# Proto-Pi.net
KiCad netlist of a schematic drawn in EAGLE
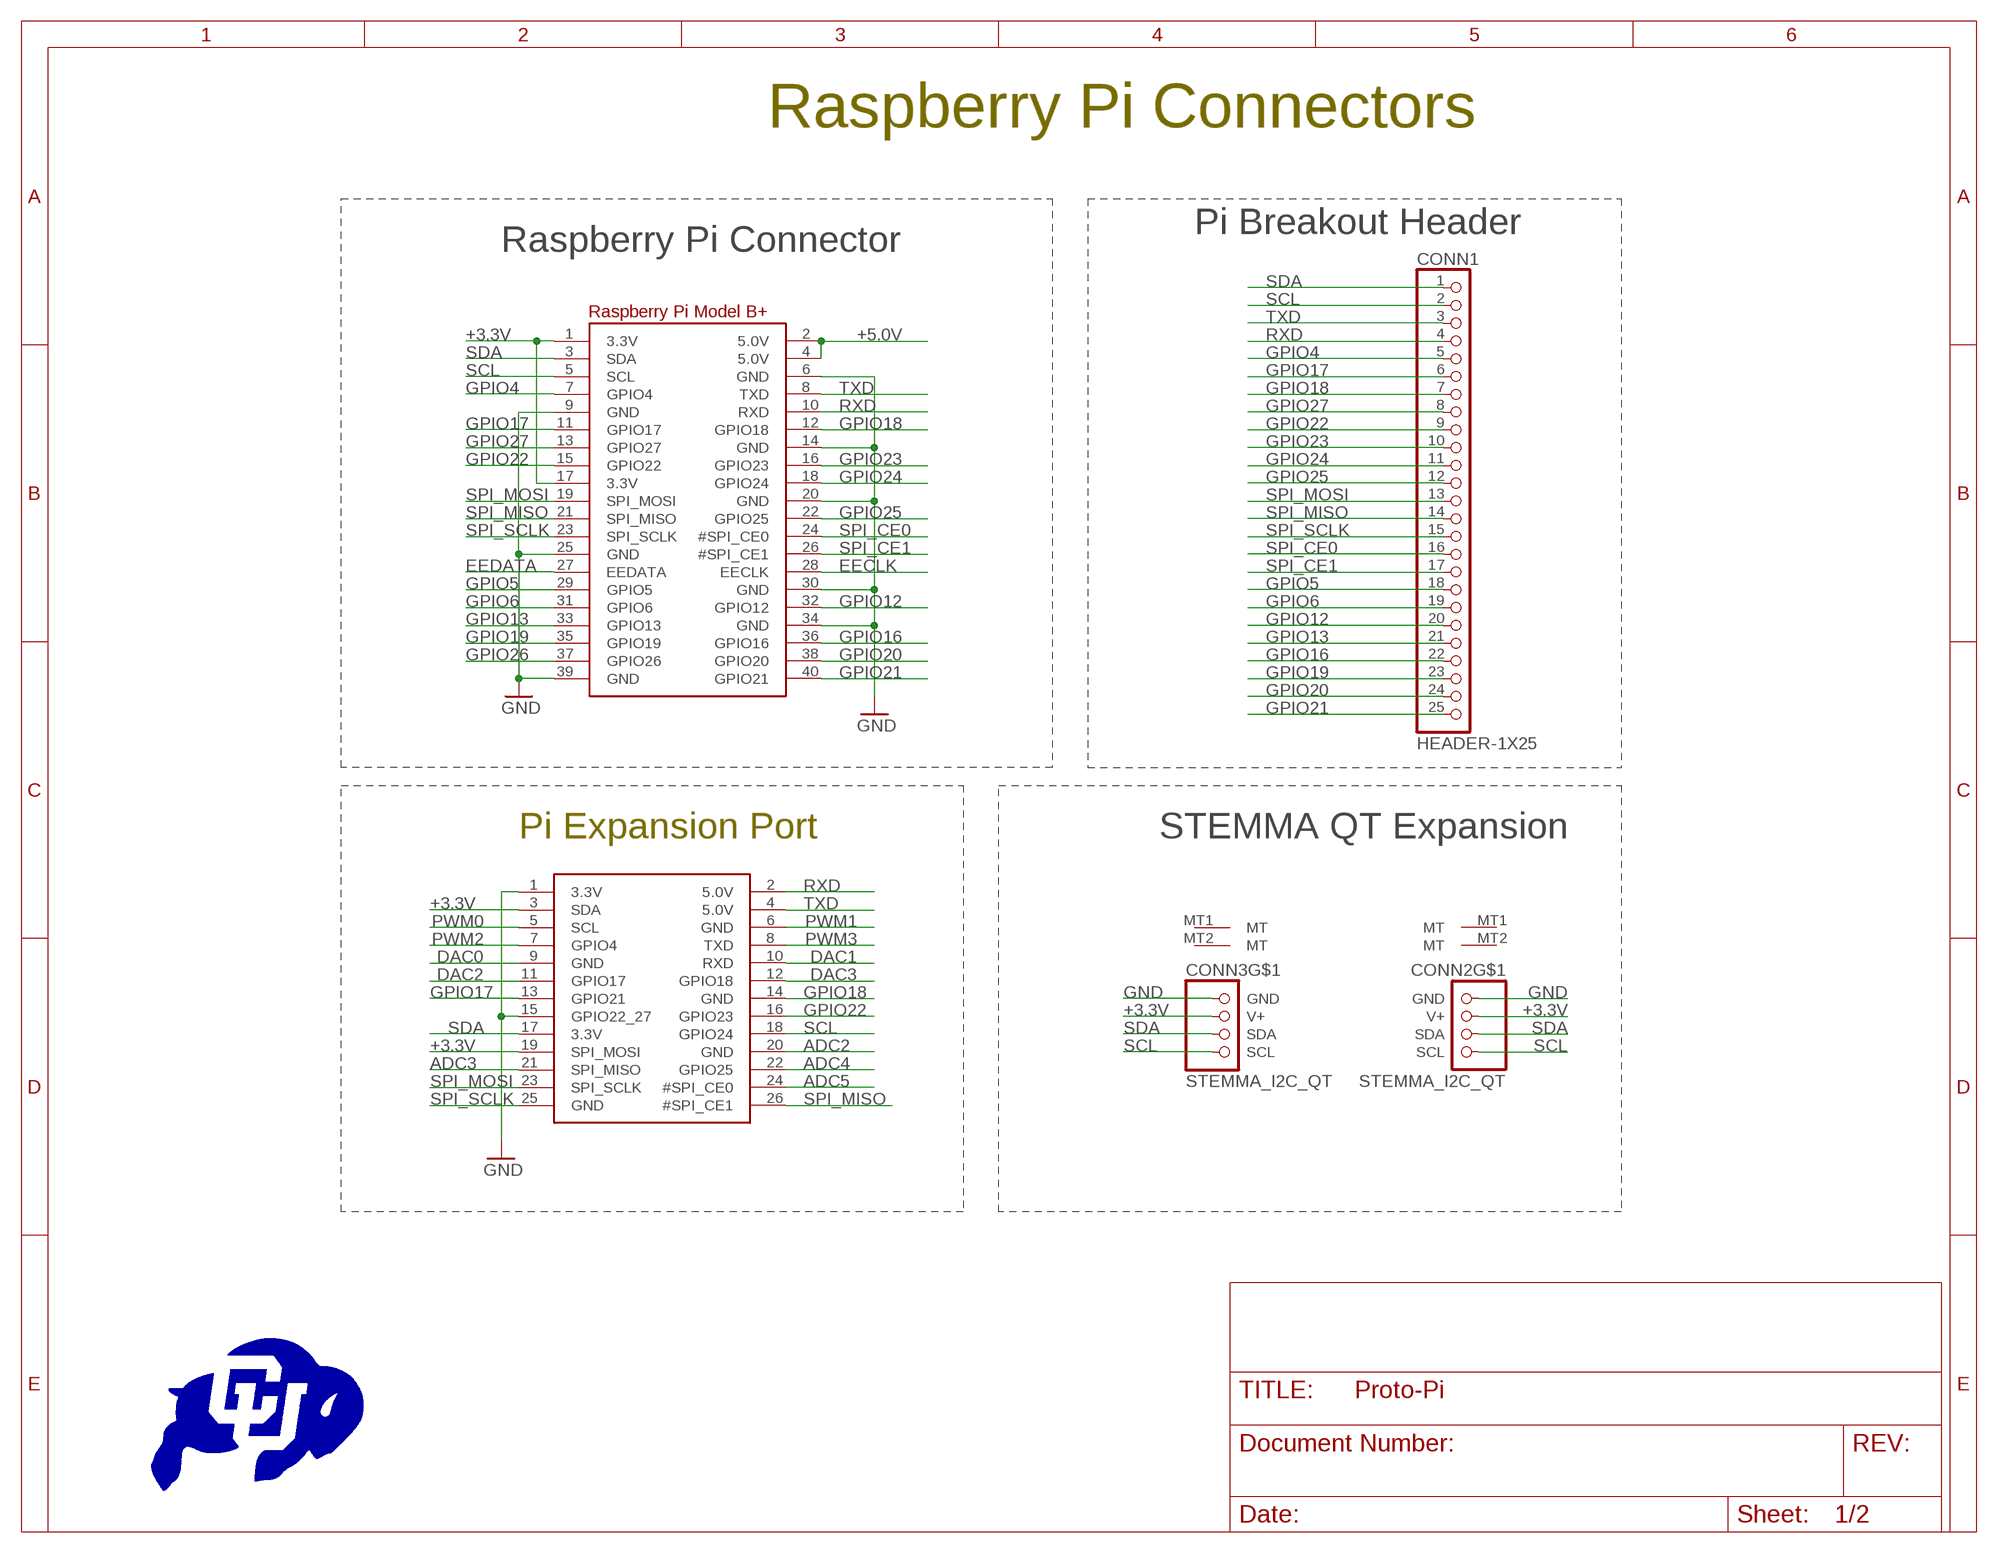
[diagram p0: schematic, sheet 1]
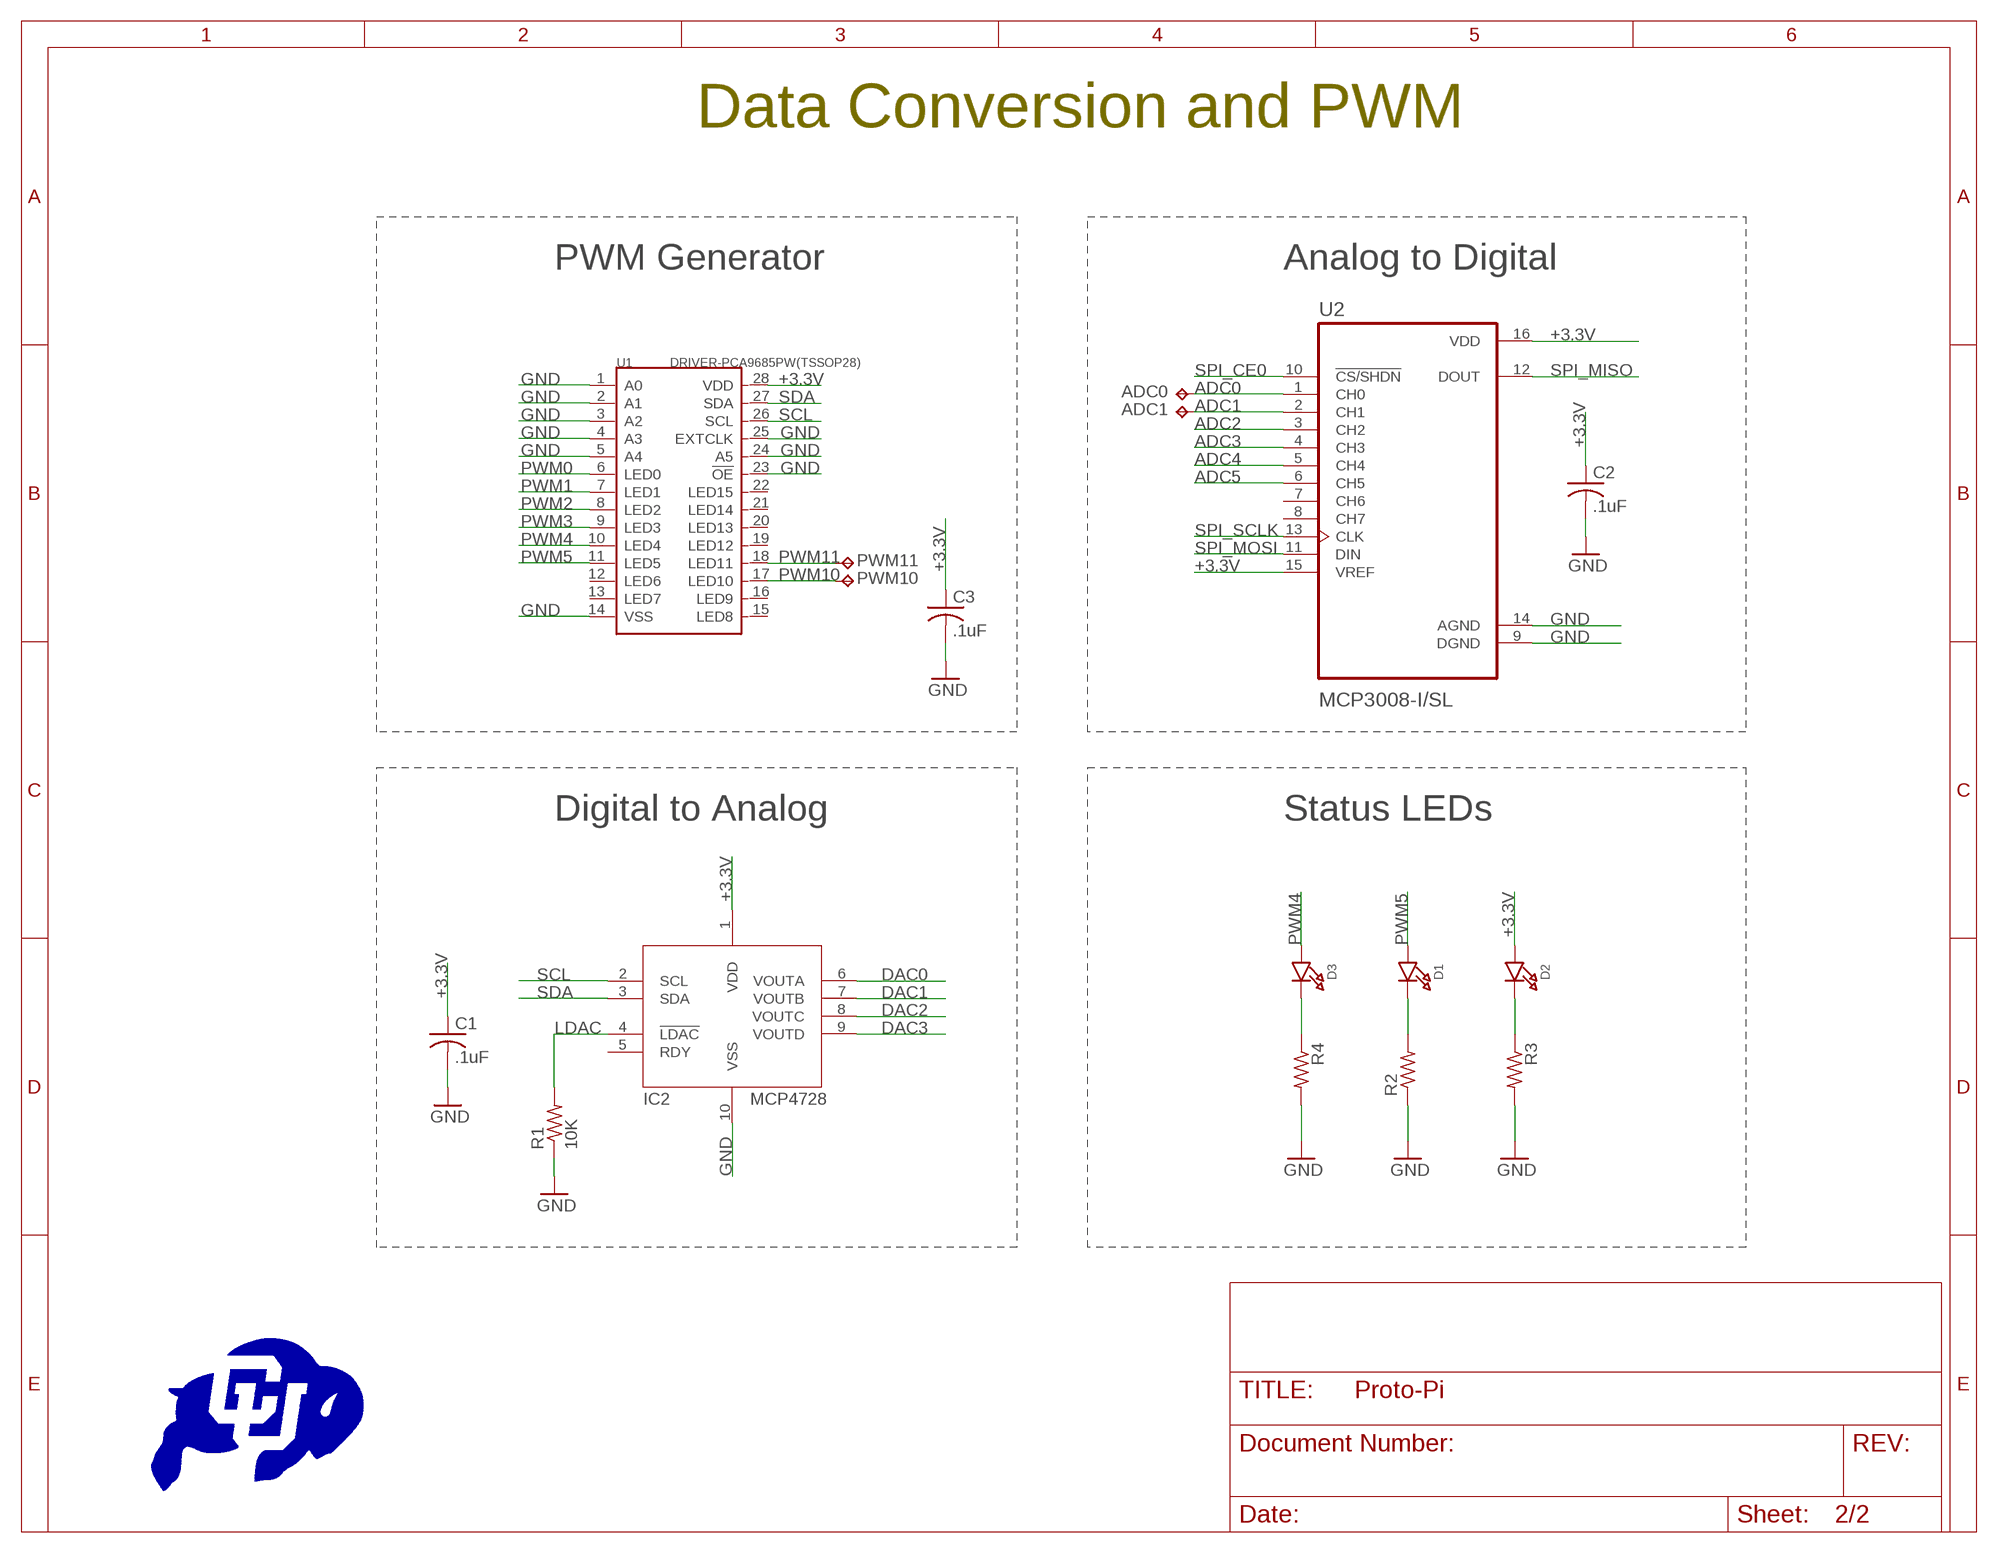
[diagram p1: schematic, sheet 2]

(export (version "E")
  (design (tool "Eeschema 10.0.6"))
  (components
    (comp (ref "CONN1")
      (value "HEADER-1X25")
      (footprint "eagle-import:1X25_ROUND_70MIL")
      (libsource (lib "eagle-import") (part "HEADER-1X25"))
    )
    (comp (ref "CONN2")
      (value "STEMMA_I2C_QT")
      (footprint "eagle-import:JST_SH4")
      (libsource (lib "eagle-import") (part "STEMMA_I2C_QT"))
    )
    (comp (ref "CONN3")
      (value "STEMMA_I2C_QT")
      (footprint "eagle-import:JST_SH4")
      (libsource (lib "eagle-import") (part "STEMMA_I2C_QT"))
    )
    (comp (ref "JP1")
      (value "RASBERRYPI_IDC")
      (footprint "eagle-import:RASBERRYPI_IDC")
      (libsource (lib "eagle-import") (part "RASBERRYPI_IDC"))
    )
    (comp (ref "P1")
      (value "ART-CU-LOGO")
      (footprint "eagle-import:CU_LOGO")
      (libsource (lib "eagle-import") (part "ART-CU-LOGO"))
    )
    (comp (ref "RPI1")
      (value "RASPBERRYPI_BPLUS_BONNETNODIM")
      (footprint "eagle-import:PI_BONNET_NODIM")
      (libsource (lib "eagle-import") (part "RASPBERRYPI_BPLUS_BONNETNODIM"))
    )
    (comp (ref "ADC0")
      (value "TPTP20R")
      (footprint "eagle-import:TP20R")
      (libsource (lib "eagle-import") (part "TPTP20R"))
    )
    (comp (ref "ADC1")
      (value "TPTP20R")
      (footprint "eagle-import:TP20R")
      (libsource (lib "eagle-import") (part "TPTP20R"))
    )
    (comp (ref "C1")
      (value ".1uF")
      (footprint "eagle-import:C0603")
      (fields (field (name "MANUFACTURER") "?"))
      (libsource (lib "eagle-import") (part "C-USC0603"))
    )
    (comp (ref "C2")
      (value ".1uF")
      (footprint "eagle-import:C0603")
      (fields (field (name "MANUFACTURER") "?"))
      (libsource (lib "eagle-import") (part "C-USC0603"))
    )
    (comp (ref "C3")
      (value ".1uF")
      (footprint "eagle-import:C0603")
      (fields (field (name "MANUFACTURER") "?"))
      (libsource (lib "eagle-import") (part "C-USC0603"))
    )
    (comp (ref "D1")
      (value "LED0603_NOOUTLINE")
      (footprint "eagle-import:CHIPLED_0603_NOOUTLINE")
      (libsource (lib "eagle-import") (part "LED0603_NOOUTLINE"))
    )
    (comp (ref "D2")
      (value "LED0603_NOOUTLINE")
      (footprint "eagle-import:CHIPLED_0603_NOOUTLINE")
      (libsource (lib "eagle-import") (part "LED0603_NOOUTLINE"))
    )
    (comp (ref "D3")
      (value "LED0603_NOOUTLINE")
      (footprint "eagle-import:CHIPLED_0603_NOOUTLINE")
      (libsource (lib "eagle-import") (part "LED0603_NOOUTLINE"))
    )
    (comp (ref "IC2")
      (value "MCP4728")
      (footprint "eagle-import:MSOP10")
      (libsource (lib "eagle-import") (part "MCP4728"))
    )
    (comp (ref "P2")
      (value "ART-CU-LOGO")
      (footprint "eagle-import:CU_LOGO")
      (libsource (lib "eagle-import") (part "ART-CU-LOGO"))
    )
    (comp (ref "PWM10")
      (value "TPTP20R")
      (footprint "eagle-import:TP20R")
      (libsource (lib "eagle-import") (part "TPTP20R"))
    )
    (comp (ref "PWM11")
      (value "TPTP20R")
      (footprint "eagle-import:TP20R")
      (libsource (lib "eagle-import") (part "TPTP20R"))
    )
    (comp (ref "R1")
      (value "10K")
      (footprint "eagle-import:R0603")
      (fields (field (name "MANUFACTURER") "?"))
      (libsource (lib "eagle-import") (part "RLC_33165012_R-US_R0603"))
    )
    (comp (ref "R2")
      (value "R-US_R0402")
      (footprint "eagle-import:R0402")
      (fields (field (name "MANUFACTURER") "?"))
      (libsource (lib "eagle-import") (part "R-US_R0402"))
    )
    (comp (ref "R3")
      (value "R-US_R0402")
      (footprint "eagle-import:R0402")
      (fields (field (name "MANUFACTURER") "?"))
      (libsource (lib "eagle-import") (part "R-US_R0402"))
    )
    (comp (ref "R4")
      (value "R-US_R0402")
      (footprint "eagle-import:R0402")
      (fields (field (name "MANUFACTURER") "?"))
      (libsource (lib "eagle-import") (part "R-US_R0402"))
    )
    (comp (ref "U1")
      (value "DRIVER-PCA9685PW(TSSOP28)")
      (footprint "eagle-import:TSSOP28-0.65-9.7X4.4MM")
      (fields (field (name "MF") "NXP USA") (field (name "MP") "PCA9685PW"))
      (libsource (lib "eagle-import") (part "DRIVER-PCA9685PW(TSSOP28)"))
    )
    (comp (ref "U2")
      (value "MCP3008-I/SL")
      (footprint "eagle-import:SOIC127P600X175-16N")
      (fields (field (name "MF") "Microchip Technology"))
      (libsource (lib "eagle-import") (part "MCP3008-I/SL"))
    )
  )
  (nets
    (net (code "1") (name "+3.3V") (class "Default")
      (node (ref "C1") (pin "1") (pinfunction "1_1") (pintype "passive"))
      (node (ref "C2") (pin "1") (pinfunction "1_1") (pintype "passive"))
      (node (ref "C3") (pin "1") (pinfunction "1_1") (pintype "passive"))
      (node (ref "CONN2") (pin "2") (pinfunction "V+_2") (pintype "passive"))
      (node (ref "CONN3") (pin "2") (pinfunction "V+_2") (pintype "passive"))
      (node (ref "D2") (pin "A") (pinfunction "A_A") (pintype "passive"))
      (node (ref "IC2") (pin "1") (pinfunction "VDD_1") (pintype "power_in"))
      (node (ref "JP1") (pin "19") (pinfunction "SPI_MOSI_19") (pintype "bidirectional"))
      (node (ref "JP1") (pin "3") (pinfunction "SDA_3") (pintype "bidirectional"))
      (node (ref "RPI1") (pin "1") (pinfunction "3.3V_1") (pintype "power_in"))
      (node (ref "RPI1") (pin "17") (pinfunction "3.3V_17") (pintype "power_in"))
      (node (ref "U1") (pin "28") (pinfunction "VDD_28") (pintype "bidirectional"))
      (node (ref "U2") (pin "15") (pinfunction "VREF_15") (pintype "input"))
      (node (ref "U2") (pin "16") (pinfunction "VDD_16") (pintype "power_in"))
    )
    (net (code "2") (name "+5.0V") (class "Default")
      (node (ref "RPI1") (pin "2") (pinfunction "5.0V_2") (pintype "power_in"))
      (node (ref "RPI1") (pin "4") (pinfunction "5.0V_4") (pintype "power_in"))
    )
    (net (code "3") (name "ADC0") (class "Default")
      (node (ref "ADC0") (pin "TP") (pinfunction "TP_TP") (pintype "input"))
      (node (ref "U2") (pin "1") (pinfunction "CH0_1") (pintype "input"))
    )
    (net (code "4") (name "ADC1") (class "Default")
      (node (ref "ADC1") (pin "TP") (pinfunction "TP_TP") (pintype "input"))
      (node (ref "U2") (pin "2") (pinfunction "CH1_2") (pintype "input"))
    )
    (net (code "5") (name "ADC2") (class "Default")
      (node (ref "JP1") (pin "20") (pinfunction "GND_20") (pintype "power_in"))
      (node (ref "U2") (pin "3") (pinfunction "CH2_3") (pintype "input"))
    )
    (net (code "6") (name "ADC3") (class "Default")
      (node (ref "JP1") (pin "21") (pinfunction "SPI_MISO_21") (pintype "input"))
      (node (ref "U2") (pin "4") (pinfunction "CH3_4") (pintype "input"))
    )
    (net (code "7") (name "ADC4") (class "Default")
      (node (ref "JP1") (pin "22") (pinfunction "GPIO25_22") (pintype "bidirectional"))
      (node (ref "U2") (pin "5") (pinfunction "CH4_5") (pintype "input"))
    )
    (net (code "8") (name "ADC5") (class "Default")
      (node (ref "JP1") (pin "24") (pinfunction "#SPI_CE0_24") (pintype "bidirectional"))
      (node (ref "U2") (pin "6") (pinfunction "CH5_6") (pintype "input"))
    )
    (net (code "9") (name "DAC0") (class "Default")
      (node (ref "IC2") (pin "6") (pinfunction "VOUTA_6") (pintype "output"))
      (node (ref "JP1") (pin "9") (pinfunction "GND_9") (pintype "power_in"))
    )
    (net (code "10") (name "DAC1") (class "Default")
      (node (ref "IC2") (pin "7") (pinfunction "VOUTB_7") (pintype "output"))
      (node (ref "JP1") (pin "10") (pinfunction "RXD_10") (pintype "input"))
    )
    (net (code "11") (name "DAC2") (class "Default")
      (node (ref "IC2") (pin "8") (pinfunction "VOUTC_8") (pintype "output"))
      (node (ref "JP1") (pin "11") (pinfunction "GPIO17_11") (pintype "bidirectional"))
    )
    (net (code "12") (name "DAC3") (class "Default")
      (node (ref "IC2") (pin "9") (pinfunction "VOUTD_9") (pintype "output"))
      (node (ref "JP1") (pin "12") (pinfunction "GPIO18_12") (pintype "bidirectional"))
    )
    (net (code "13") (name "EECLK") (class "Default")
      (node (ref "RPI1") (pin "28") (pinfunction "EECLK_28") (pintype "bidirectional"))
    )
    (net (code "14") (name "EEDATA") (class "Default")
      (node (ref "RPI1") (pin "27") (pinfunction "EEDATA_27") (pintype "bidirectional"))
    )
    (net (code "15") (name "GND") (class "Default")
      (node (ref "C1") (pin "2") (pinfunction "2_2") (pintype "passive"))
      (node (ref "C2") (pin "2") (pinfunction "2_2") (pintype "passive"))
      (node (ref "C3") (pin "2") (pinfunction "2_2") (pintype "passive"))
      (node (ref "CONN2") (pin "1") (pinfunction "GND_1") (pintype "passive"))
      (node (ref "CONN3") (pin "1") (pinfunction "GND_1") (pintype "passive"))
      (node (ref "IC2") (pin "10") (pinfunction "VSS_10") (pintype "power_in"))
      (node (ref "JP1") (pin "1") (pinfunction "3.3V_1") (pintype "power_in"))
      (node (ref "JP1") (pin "15") (pinfunction "GPIO22_27_15") (pintype "bidirectional"))
      (node (ref "R1") (pin "1") (pinfunction "1_1") (pintype "passive"))
      (node (ref "R2") (pin "1") (pinfunction "1_1") (pintype "passive"))
      (node (ref "R3") (pin "2") (pinfunction "2_2") (pintype "passive"))
      (node (ref "R4") (pin "2") (pinfunction "2_2") (pintype "passive"))
      (node (ref "RPI1") (pin "14") (pinfunction "GND_14") (pintype "power_in"))
      (node (ref "RPI1") (pin "20") (pinfunction "GND_20") (pintype "power_in"))
      (node (ref "RPI1") (pin "25") (pinfunction "GND_25") (pintype "power_in"))
      (node (ref "RPI1") (pin "30") (pinfunction "GND_30") (pintype "power_in"))
      (node (ref "RPI1") (pin "34") (pinfunction "GND_34") (pintype "power_in"))
      (node (ref "RPI1") (pin "39") (pinfunction "GND_39") (pintype "power_in"))
      (node (ref "RPI1") (pin "6") (pinfunction "GND_6") (pintype "power_in"))
      (node (ref "RPI1") (pin "9") (pinfunction "GND_9") (pintype "power_in"))
      (node (ref "U1") (pin "1") (pinfunction "A0_1") (pintype "bidirectional"))
      (node (ref "U1") (pin "14") (pinfunction "VSS_14") (pintype "bidirectional"))
      (node (ref "U1") (pin "2") (pinfunction "A1_2") (pintype "bidirectional"))
      (node (ref "U1") (pin "23") (pinfunction "~{OE}_23") (pintype "bidirectional"))
      (node (ref "U1") (pin "24") (pinfunction "A5_24") (pintype "bidirectional"))
      (node (ref "U1") (pin "25") (pinfunction "EXTCLK_25") (pintype "bidirectional"))
      (node (ref "U1") (pin "3") (pinfunction "A2_3") (pintype "bidirectional"))
      (node (ref "U1") (pin "4") (pinfunction "A3_4") (pintype "bidirectional"))
      (node (ref "U1") (pin "5") (pinfunction "A4_5") (pintype "bidirectional"))
      (node (ref "U2") (pin "14") (pinfunction "AGND_14") (pintype "power_in"))
      (node (ref "U2") (pin "9") (pinfunction "DGND_9") (pintype "power_in"))
    )
    (net (code "16") (name "GPIO4") (class "Default")
      (node (ref "CONN1") (pin "5") (pinfunction "5_5") (pintype "passive"))
      (node (ref "RPI1") (pin "7") (pinfunction "GPIO4_7") (pintype "bidirectional"))
    )
    (net (code "17") (name "GPIO5") (class "Default")
      (node (ref "CONN1") (pin "18") (pinfunction "18_18") (pintype "passive"))
      (node (ref "RPI1") (pin "29") (pinfunction "GPIO5_29") (pintype "bidirectional"))
    )
    (net (code "18") (name "GPIO6") (class "Default")
      (node (ref "CONN1") (pin "19") (pinfunction "19_19") (pintype "passive"))
      (node (ref "RPI1") (pin "31") (pinfunction "GPIO6_31") (pintype "bidirectional"))
    )
    (net (code "19") (name "GPIO12") (class "Default")
      (node (ref "CONN1") (pin "20") (pinfunction "20_20") (pintype "passive"))
      (node (ref "RPI1") (pin "32") (pinfunction "GPIO12_32") (pintype "bidirectional"))
    )
    (net (code "20") (name "GPIO13") (class "Default")
      (node (ref "CONN1") (pin "21") (pinfunction "21_21") (pintype "passive"))
      (node (ref "RPI1") (pin "33") (pinfunction "GPIO13_33") (pintype "bidirectional"))
    )
    (net (code "21") (name "GPIO16") (class "Default")
      (node (ref "CONN1") (pin "22") (pinfunction "22_22") (pintype "passive"))
      (node (ref "RPI1") (pin "36") (pinfunction "GPIO16_36") (pintype "bidirectional"))
    )
    (net (code "22") (name "GPIO17") (class "Default")
      (node (ref "CONN1") (pin "6") (pinfunction "6_6") (pintype "passive"))
      (node (ref "JP1") (pin "13") (pinfunction "GPIO21_13") (pintype "bidirectional"))
      (node (ref "RPI1") (pin "11") (pinfunction "GPIO17_11") (pintype "bidirectional"))
    )
    (net (code "23") (name "GPIO18") (class "Default")
      (node (ref "CONN1") (pin "7") (pinfunction "7_7") (pintype "passive"))
      (node (ref "JP1") (pin "14") (pinfunction "GND_14") (pintype "power_in"))
      (node (ref "RPI1") (pin "12") (pinfunction "GPIO18_12") (pintype "bidirectional"))
    )
    (net (code "24") (name "GPIO19") (class "Default")
      (node (ref "CONN1") (pin "23") (pinfunction "23_23") (pintype "passive"))
      (node (ref "RPI1") (pin "35") (pinfunction "GPIO19_35") (pintype "bidirectional"))
    )
    (net (code "25") (name "GPIO20") (class "Default")
      (node (ref "CONN1") (pin "24") (pinfunction "24_24") (pintype "passive"))
      (node (ref "RPI1") (pin "38") (pinfunction "GPIO20_38") (pintype "bidirectional"))
    )
    (net (code "26") (name "GPIO21") (class "Default")
      (node (ref "CONN1") (pin "25") (pinfunction "25_25") (pintype "passive"))
      (node (ref "RPI1") (pin "40") (pinfunction "GPIO21_40") (pintype "bidirectional"))
    )
    (net (code "27") (name "GPIO22") (class "Default")
      (node (ref "CONN1") (pin "9") (pinfunction "9_9") (pintype "passive"))
      (node (ref "JP1") (pin "16") (pinfunction "GPIO23_16") (pintype "bidirectional"))
      (node (ref "RPI1") (pin "15") (pinfunction "GPIO22_15") (pintype "bidirectional"))
    )
    (net (code "28") (name "GPIO23") (class "Default")
      (node (ref "CONN1") (pin "10") (pinfunction "10_10") (pintype "passive"))
      (node (ref "RPI1") (pin "16") (pinfunction "GPIO23_16") (pintype "bidirectional"))
    )
    (net (code "29") (name "GPIO24") (class "Default")
      (node (ref "CONN1") (pin "11") (pinfunction "11_11") (pintype "passive"))
      (node (ref "RPI1") (pin "18") (pinfunction "GPIO24_18") (pintype "bidirectional"))
    )
    (net (code "30") (name "GPIO25") (class "Default")
      (node (ref "CONN1") (pin "12") (pinfunction "12_12") (pintype "passive"))
      (node (ref "RPI1") (pin "22") (pinfunction "GPIO25_22") (pintype "bidirectional"))
    )
    (net (code "31") (name "GPIO26") (class "Default")
      (node (ref "RPI1") (pin "37") (pinfunction "GPIO26_37") (pintype "bidirectional"))
    )
    (net (code "32") (name "GPIO27") (class "Default")
      (node (ref "CONN1") (pin "8") (pinfunction "8_8") (pintype "passive"))
      (node (ref "RPI1") (pin "13") (pinfunction "GPIO27_13") (pintype "bidirectional"))
    )
    (net (code "33") (name "LDAC") (class "Default")
      (node (ref "IC2") (pin "4") (pinfunction "~{LDAC}_4") (pintype "input"))
      (node (ref "R1") (pin "2") (pinfunction "2_2") (pintype "passive"))
    )
    (net (code "34") (name "Net-(D1-PadC)") (class "Default")
      (node (ref "D1") (pin "C") (pinfunction "C_C") (pintype "passive"))
      (node (ref "R2") (pin "2") (pinfunction "2_2") (pintype "passive"))
    )
    (net (code "35") (name "Net-(D2-PadC)") (class "Default")
      (node (ref "D2") (pin "C") (pinfunction "C_C") (pintype "passive"))
      (node (ref "R3") (pin "1") (pinfunction "1_1") (pintype "passive"))
    )
    (net (code "36") (name "Net-(D3-PadC)") (class "Default")
      (node (ref "D3") (pin "C") (pinfunction "C_C") (pintype "passive"))
      (node (ref "R4") (pin "1") (pinfunction "1_1") (pintype "passive"))
    )
    (net (code "37") (name "PWM0") (class "Default")
      (node (ref "JP1") (pin "5") (pinfunction "SCL_5") (pintype "bidirectional"))
      (node (ref "U1") (pin "6") (pinfunction "LED0_6") (pintype "bidirectional"))
    )
    (net (code "38") (name "PWM1") (class "Default")
      (node (ref "JP1") (pin "6") (pinfunction "GND_6") (pintype "power_in"))
      (node (ref "U1") (pin "7") (pinfunction "LED1_7") (pintype "bidirectional"))
    )
    (net (code "39") (name "PWM2") (class "Default")
      (node (ref "JP1") (pin "7") (pinfunction "GPIO4_7") (pintype "bidirectional"))
      (node (ref "U1") (pin "8") (pinfunction "LED2_8") (pintype "bidirectional"))
    )
    (net (code "40") (name "PWM3") (class "Default")
      (node (ref "JP1") (pin "8") (pinfunction "TXD_8") (pintype "output"))
      (node (ref "U1") (pin "9") (pinfunction "LED3_9") (pintype "bidirectional"))
    )
    (net (code "41") (name "PWM4") (class "Default")
      (node (ref "D3") (pin "A") (pinfunction "A_A") (pintype "passive"))
      (node (ref "U1") (pin "10") (pinfunction "LED4_10") (pintype "bidirectional"))
    )
    (net (code "42") (name "PWM5") (class "Default")
      (node (ref "D1") (pin "A") (pinfunction "A_A") (pintype "passive"))
      (node (ref "U1") (pin "11") (pinfunction "LED5_11") (pintype "bidirectional"))
    )
    (net (code "43") (name "PWM10") (class "Default")
      (node (ref "PWM10") (pin "TP") (pinfunction "TP_TP") (pintype "input"))
      (node (ref "U1") (pin "17") (pinfunction "LED10_17") (pintype "bidirectional"))
    )
    (net (code "44") (name "PWM11") (class "Default")
      (node (ref "PWM11") (pin "TP") (pinfunction "TP_TP") (pintype "input"))
      (node (ref "U1") (pin "18") (pinfunction "LED11_18") (pintype "bidirectional"))
    )
    (net (code "45") (name "RXD") (class "Default")
      (node (ref "CONN1") (pin "4") (pinfunction "4_4") (pintype "passive"))
      (node (ref "JP1") (pin "2") (pinfunction "5.0V_2") (pintype "power_in"))
      (node (ref "RPI1") (pin "10") (pinfunction "RXD_10") (pintype "bidirectional"))
    )
    (net (code "46") (name "SCL") (class "Default")
      (node (ref "CONN1") (pin "2") (pinfunction "2_2") (pintype "passive"))
      (node (ref "CONN2") (pin "4") (pinfunction "SCL_4") (pintype "passive"))
      (node (ref "CONN3") (pin "4") (pinfunction "SCL_4") (pintype "passive"))
      (node (ref "IC2") (pin "2") (pinfunction "SCL_2") (pintype "bidirectional"))
      (node (ref "JP1") (pin "18") (pinfunction "GPIO24_18") (pintype "bidirectional"))
      (node (ref "RPI1") (pin "5") (pinfunction "SCL_5") (pintype "bidirectional"))
      (node (ref "U1") (pin "26") (pinfunction "SCL_26") (pintype "bidirectional"))
    )
    (net (code "47") (name "SDA") (class "Default")
      (node (ref "CONN1") (pin "1") (pinfunction "1_1") (pintype "passive"))
      (node (ref "CONN2") (pin "3") (pinfunction "SDA_3") (pintype "passive"))
      (node (ref "CONN3") (pin "3") (pinfunction "SDA_3") (pintype "passive"))
      (node (ref "IC2") (pin "3") (pinfunction "SDA_3") (pintype "bidirectional"))
      (node (ref "JP1") (pin "17") (pinfunction "3.3V_17") (pintype "power_in"))
      (node (ref "RPI1") (pin "3") (pinfunction "SDA_3") (pintype "bidirectional"))
      (node (ref "U1") (pin "27") (pinfunction "SDA_27") (pintype "bidirectional"))
    )
    (net (code "48") (name "SPI_CE0") (class "Default")
      (node (ref "CONN1") (pin "16") (pinfunction "16_16") (pintype "passive"))
      (node (ref "RPI1") (pin "24") (pinfunction "#SPI_CE0_24") (pintype "bidirectional"))
      (node (ref "U2") (pin "10") (pinfunction "~{CS/SHDN}_10") (pintype "input"))
    )
    (net (code "49") (name "SPI_CE1") (class "Default")
      (node (ref "CONN1") (pin "17") (pinfunction "17_17") (pintype "passive"))
      (node (ref "RPI1") (pin "26") (pinfunction "#SPI_CE1_26") (pintype "bidirectional"))
    )
    (net (code "50") (name "SPI_MISO") (class "Default")
      (node (ref "CONN1") (pin "14") (pinfunction "14_14") (pintype "passive"))
      (node (ref "JP1") (pin "26") (pinfunction "#SPI_CE1_26") (pintype "bidirectional"))
      (node (ref "RPI1") (pin "21") (pinfunction "SPI_MISO_21") (pintype "bidirectional"))
      (node (ref "U2") (pin "12") (pinfunction "DOUT_12") (pintype "output"))
    )
    (net (code "51") (name "SPI_MOSI") (class "Default")
      (node (ref "CONN1") (pin "13") (pinfunction "13_13") (pintype "passive"))
      (node (ref "JP1") (pin "23") (pinfunction "SPI_SCLK_23") (pintype "bidirectional"))
      (node (ref "RPI1") (pin "19") (pinfunction "SPI_MOSI_19") (pintype "bidirectional"))
      (node (ref "U2") (pin "11") (pinfunction "DIN_11") (pintype "input"))
    )
    (net (code "52") (name "SPI_SCLK") (class "Default")
      (node (ref "CONN1") (pin "15") (pinfunction "15_15") (pintype "passive"))
      (node (ref "JP1") (pin "25") (pinfunction "GND_25") (pintype "power_in"))
      (node (ref "RPI1") (pin "23") (pinfunction "SPI_SCLK_23") (pintype "bidirectional"))
      (node (ref "U2") (pin "13") (pinfunction "CLK_13") (pintype "input"))
    )
    (net (code "53") (name "TXD") (class "Default")
      (node (ref "CONN1") (pin "3") (pinfunction "3_3") (pintype "passive"))
      (node (ref "JP1") (pin "4") (pinfunction "5.0V_4") (pintype "power_in"))
      (node (ref "RPI1") (pin "8") (pinfunction "TXD_8") (pintype "bidirectional"))
    )
    (net (code "54") (name "unconnected-(CONN2B-MT-PadMT1)") (class "Default")
      (node (ref "CONN2") (pin "MT1") (pinfunction "MT_MT1") (pintype "bidirectional"))
    )
    (net (code "55") (name "unconnected-(CONN2C-MT-PadMT2)") (class "Default")
      (node (ref "CONN2") (pin "MT2") (pinfunction "MT_MT2") (pintype "bidirectional"))
    )
    (net (code "56") (name "unconnected-(CONN3B-MT-PadMT1)") (class "Default")
      (node (ref "CONN3") (pin "MT1") (pinfunction "MT_MT1") (pintype "bidirectional"))
    )
    (net (code "57") (name "unconnected-(CONN3C-MT-PadMT2)") (class "Default")
      (node (ref "CONN3") (pin "MT2") (pinfunction "MT_MT2") (pintype "bidirectional"))
    )
    (net (code "58") (name "unconnected-(IC2-RDY-Pad5)") (class "Default")
      (node (ref "IC2") (pin "5") (pinfunction "RDY_5") (pintype "output"))
    )
    (net (code "59") (name "unconnected-(U1-LED6-Pad12)") (class "Default")
      (node (ref "U1") (pin "12") (pinfunction "LED6_12") (pintype "bidirectional"))
    )
    (net (code "60") (name "unconnected-(U1-LED7-Pad13)") (class "Default")
      (node (ref "U1") (pin "13") (pinfunction "LED7_13") (pintype "bidirectional"))
    )
    (net (code "61") (name "unconnected-(U1-LED8-Pad15)") (class "Default")
      (node (ref "U1") (pin "15") (pinfunction "LED8_15") (pintype "bidirectional"))
    )
    (net (code "62") (name "unconnected-(U1-LED9-Pad16)") (class "Default")
      (node (ref "U1") (pin "16") (pinfunction "LED9_16") (pintype "bidirectional"))
    )
    (net (code "63") (name "unconnected-(U1-LED12-Pad19)") (class "Default")
      (node (ref "U1") (pin "19") (pinfunction "LED12_19") (pintype "bidirectional"))
    )
    (net (code "64") (name "unconnected-(U1-LED13-Pad20)") (class "Default")
      (node (ref "U1") (pin "20") (pinfunction "LED13_20") (pintype "bidirectional"))
    )
    (net (code "65") (name "unconnected-(U1-LED14-Pad21)") (class "Default")
      (node (ref "U1") (pin "21") (pinfunction "LED14_21") (pintype "bidirectional"))
    )
    (net (code "66") (name "unconnected-(U1-LED15-Pad22)") (class "Default")
      (node (ref "U1") (pin "22") (pinfunction "LED15_22") (pintype "bidirectional"))
    )
    (net (code "67") (name "unconnected-(U2-CH6-Pad7)") (class "Default")
      (node (ref "U2") (pin "7") (pinfunction "CH6_7") (pintype "input"))
    )
    (net (code "68") (name "unconnected-(U2-CH7-Pad8)") (class "Default")
      (node (ref "U2") (pin "8") (pinfunction "CH7_8") (pintype "input"))
    )
  )
)
